# zero_board.net
KiCad netlist of a schematic drawn in EAGLE
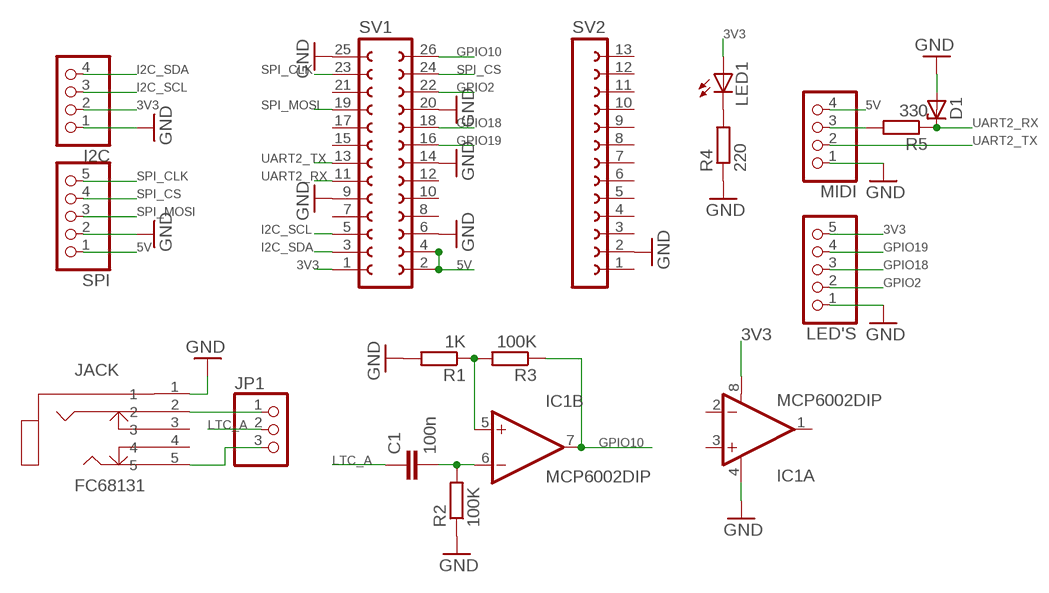
[diagram p0: schematic, sheet 1]

(export (version "E")
  (design (tool "Eeschema 10.0.6"))
  (components
    (comp (ref "C1")
      (value "100n")
      (footprint "eagle-import:C050-024X044")
      (libsource (lib "eagle-import") (part "C-EU050-024X044"))
    )
    (comp (ref "D1")
      (value "ZENER-DIODEZD-2.5")
      (footprint "eagle-import:ZDIO-2.5")
      (libsource (lib "eagle-import") (part "ZENER-DIODEZD-2.5"))
    )
    (comp (ref "I2C")
      (value "PINHD-1X4")
      (footprint "eagle-import:1X04")
      (libsource (lib "eagle-import") (part "PINHD-1X4"))
    )
    (comp (ref "IC1")
      (value "MCP6002DIP")
      (footprint "eagle-import:DIP08")
      (libsource (lib "eagle-import") (part "MCP6002DIP"))
    )
    (comp (ref "JACK")
      (value "FC68131")
      (footprint "eagle-import:FC68131-5P")
      (libsource (lib "eagle-import") (part "FC68131"))
    )
    (comp (ref "JP1")
      (value "PINHD-1X3")
      (footprint "eagle-import:1X03")
      (libsource (lib "eagle-import") (part "PINHD-1X3"))
    )
    (comp (ref "LED'S")
      (value "PINHD-1X5")
      (footprint "eagle-import:1X05")
      (libsource (lib "eagle-import") (part "PINHD-1X5"))
    )
    (comp (ref "LED1")
      (value "LED3MM")
      (footprint "eagle-import:LED3MM")
      (libsource (lib "eagle-import") (part "LED3MM"))
    )
    (comp (ref "MIDI")
      (value "PINHD-1X4")
      (footprint "eagle-import:1X04")
      (libsource (lib "eagle-import") (part "PINHD-1X4"))
    )
    (comp (ref "R1")
      (value "1K")
      (footprint "eagle-import:0204_5")
      (libsource (lib "eagle-import") (part "R-EU_0204/5"))
    )
    (comp (ref "R2")
      (value "100K")
      (footprint "eagle-import:0204_5")
      (libsource (lib "eagle-import") (part "R-EU_0204/5"))
    )
    (comp (ref "R3")
      (value "100K")
      (footprint "eagle-import:0204_5")
      (libsource (lib "eagle-import") (part "R-EU_0204/5"))
    )
    (comp (ref "R4")
      (value "220")
      (footprint "eagle-import:0204_5")
      (libsource (lib "eagle-import") (part "R-EU_0204/5"))
    )
    (comp (ref "R5")
      (value "330")
      (footprint "eagle-import:0204V")
      (libsource (lib "eagle-import") (part "R-EU_0204/2V"))
    )
    (comp (ref "SPI")
      (value "PINHD-1X5")
      (footprint "eagle-import:1X05")
      (libsource (lib "eagle-import") (part "PINHD-1X5"))
    )
    (comp (ref "SV1")
      (value "FE13-2")
      (footprint "eagle-import:FE13-2")
      (libsource (lib "eagle-import") (part "FE13-2"))
    )
    (comp (ref "SV2")
      (value "FE13-1")
      (footprint "eagle-import:FE13")
      (libsource (lib "eagle-import") (part "FE13-1"))
    )
  )
  (nets
    (net (code "1") (name "/3V3") (class "Default")
      (node (ref "I2C") (pin "2") (pinfunction "2_2") (pintype "passive"))
      (node (ref "IC1") (pin "8") (pinfunction "V+_8") (pintype "power_in"))
      (node (ref "LED'S") (pin "5") (pinfunction "5_5") (pintype "passive"))
      (node (ref "LED1") (pin "A") (pinfunction "A_A") (pintype "passive"))
      (node (ref "SV1") (pin "1") (pinfunction "1_1") (pintype "passive"))
    )
    (net (code "2") (name "/5V") (class "Default")
      (node (ref "MIDI") (pin "4") (pinfunction "4_4") (pintype "passive"))
      (node (ref "SPI") (pin "1") (pinfunction "1_1") (pintype "passive"))
      (node (ref "SV1") (pin "2") (pinfunction "2_2") (pintype "passive"))
      (node (ref "SV1") (pin "4") (pinfunction "4_4") (pintype "passive"))
    )
    (net (code "3") (name "/GPIO2") (class "Default")
      (node (ref "LED'S") (pin "2") (pinfunction "2_2") (pintype "passive"))
      (node (ref "SV1") (pin "22") (pinfunction "22_22") (pintype "passive"))
    )
    (net (code "4") (name "/GPIO10") (class "Default")
      (node (ref "IC1") (pin "7") (pinfunction "OUT_7") (pintype "output"))
      (node (ref "R3") (pin "1") (pinfunction "1_1") (pintype "passive"))
      (node (ref "SV1") (pin "26") (pinfunction "26_26") (pintype "passive"))
    )
    (net (code "5") (name "/GPIO18") (class "Default")
      (node (ref "LED'S") (pin "3") (pinfunction "3_3") (pintype "passive"))
      (node (ref "SV1") (pin "18") (pinfunction "18_18") (pintype "passive"))
    )
    (net (code "6") (name "/GPIO19") (class "Default")
      (node (ref "LED'S") (pin "4") (pinfunction "4_4") (pintype "passive"))
      (node (ref "SV1") (pin "16") (pinfunction "16_16") (pintype "passive"))
    )
    (net (code "7") (name "/I2C_SCL") (class "Default")
      (node (ref "I2C") (pin "3") (pinfunction "3_3") (pintype "passive"))
      (node (ref "SV1") (pin "5") (pinfunction "5_5") (pintype "passive"))
    )
    (net (code "8") (name "/I2C_SDA") (class "Default")
      (node (ref "I2C") (pin "4") (pinfunction "4_4") (pintype "passive"))
      (node (ref "SV1") (pin "3") (pinfunction "3_3") (pintype "passive"))
    )
    (net (code "9") (name "/LTC_A") (class "Default")
      (node (ref "C1") (pin "1") (pinfunction "1_1") (pintype "passive"))
      (node (ref "JP1") (pin "2") (pinfunction "2_2") (pintype "passive"))
    )
    (net (code "10") (name "/SPI_CLK") (class "Default")
      (node (ref "SPI") (pin "5") (pinfunction "5_5") (pintype "passive"))
      (node (ref "SV1") (pin "23") (pinfunction "23_23") (pintype "passive"))
    )
    (net (code "11") (name "/SPI_CS") (class "Default")
      (node (ref "SPI") (pin "4") (pinfunction "4_4") (pintype "passive"))
      (node (ref "SV1") (pin "24") (pinfunction "24_24") (pintype "passive"))
    )
    (net (code "12") (name "/SPI_MOSI") (class "Default")
      (node (ref "SPI") (pin "3") (pinfunction "3_3") (pintype "passive"))
      (node (ref "SV1") (pin "19") (pinfunction "19_19") (pintype "passive"))
    )
    (net (code "13") (name "/UART2_RX") (class "Default")
      (node (ref "D1") (pin "C") (pinfunction "C_C") (pintype "passive"))
      (node (ref "R5") (pin "1") (pinfunction "1_1") (pintype "passive"))
      (node (ref "SV1") (pin "11") (pinfunction "11_11") (pintype "passive"))
    )
    (net (code "14") (name "/UART2_TX") (class "Default")
      (node (ref "MIDI") (pin "2") (pinfunction "2_2") (pintype "passive"))
      (node (ref "SV1") (pin "13") (pinfunction "13_13") (pintype "passive"))
    )
    (net (code "15") (name "GND") (class "Default")
      (node (ref "D1") (pin "A") (pinfunction "A_A") (pintype "passive"))
      (node (ref "I2C") (pin "1") (pinfunction "1_1") (pintype "passive"))
      (node (ref "IC1") (pin "4") (pinfunction "V-_4") (pintype "power_in"))
      (node (ref "JACK") (pin "1") (pinfunction "1_1") (pintype "bidirectional"))
      (node (ref "LED'S") (pin "1") (pinfunction "1_1") (pintype "passive"))
      (node (ref "MIDI") (pin "1") (pinfunction "1_1") (pintype "passive"))
      (node (ref "R1") (pin "2") (pinfunction "2_2") (pintype "passive"))
      (node (ref "R2") (pin "1") (pinfunction "1_1") (pintype "passive"))
      (node (ref "R4") (pin "1") (pinfunction "1_1") (pintype "passive"))
      (node (ref "SPI") (pin "2") (pinfunction "2_2") (pintype "passive"))
      (node (ref "SV1") (pin "14") (pinfunction "14_14") (pintype "passive"))
      (node (ref "SV1") (pin "20") (pinfunction "20_20") (pintype "passive"))
      (node (ref "SV1") (pin "25") (pinfunction "25_25") (pintype "passive"))
      (node (ref "SV1") (pin "6") (pinfunction "6_6") (pintype "passive"))
      (node (ref "SV1") (pin "9") (pinfunction "9_9") (pintype "passive"))
      (node (ref "SV2") (pin "2") (pinfunction "2_2") (pintype "passive"))
    )
    (net (code "16") (name "Net-(IC1B-+IN)") (class "Default")
      (node (ref "IC1") (pin "5") (pinfunction "+IN_5") (pintype "input"))
      (node (ref "R1") (pin "1") (pinfunction "1_1") (pintype "passive"))
      (node (ref "R3") (pin "2") (pinfunction "2_2") (pintype "passive"))
    )
    (net (code "17") (name "Net-(IC1B--IN)") (class "Default")
      (node (ref "C1") (pin "2") (pinfunction "2_2") (pintype "passive"))
      (node (ref "IC1") (pin "6") (pinfunction "-IN_6") (pintype "input"))
      (node (ref "R2") (pin "2") (pinfunction "2_2") (pintype "passive"))
    )
    (net (code "18") (name "Net-(JACK-Pad2)") (class "Default")
      (node (ref "JACK") (pin "2") (pinfunction "2_2") (pintype "bidirectional"))
      (node (ref "JP1") (pin "1") (pinfunction "1_1") (pintype "passive"))
    )
    (net (code "19") (name "Net-(JACK-Pad5)") (class "Default")
      (node (ref "JACK") (pin "5") (pinfunction "5_5") (pintype "bidirectional"))
      (node (ref "JP1") (pin "3") (pinfunction "3_3") (pintype "passive"))
    )
    (net (code "20") (name "Net-(LED1-C)") (class "Default")
      (node (ref "LED1") (pin "K") (pinfunction "C_K") (pintype "passive"))
      (node (ref "R4") (pin "2") (pinfunction "2_2") (pintype "passive"))
    )
    (net (code "21") (name "Net-(MIDI-Pad3)") (class "Default")
      (node (ref "MIDI") (pin "3") (pinfunction "3_3") (pintype "passive"))
      (node (ref "R5") (pin "2") (pinfunction "2_2") (pintype "passive"))
    )
    (net (code "22") (name "unconnected-(IC1A-+IN-Pad3)") (class "Default")
      (node (ref "IC1") (pin "3") (pinfunction "+IN_3") (pintype "input"))
    )
    (net (code "23") (name "unconnected-(IC1A--IN-Pad2)") (class "Default")
      (node (ref "IC1") (pin "2") (pinfunction "-IN_2") (pintype "input"))
    )
    (net (code "24") (name "unconnected-(IC1A-OUT-Pad1)") (class "Default")
      (node (ref "IC1") (pin "1") (pinfunction "OUT_1") (pintype "output"))
    )
    (net (code "25") (name "unconnected-(JACK-Pad3)") (class "Default")
      (node (ref "JACK") (pin "3") (pinfunction "3_3") (pintype "bidirectional"))
    )
    (net (code "26") (name "unconnected-(JACK-Pad4)") (class "Default")
      (node (ref "JACK") (pin "4") (pinfunction "4_4") (pintype "bidirectional"))
    )
    (net (code "27") (name "unconnected-(SV1-Pad7)") (class "Default")
      (node (ref "SV1") (pin "7") (pinfunction "7_7") (pintype "passive"))
    )
    (net (code "28") (name "unconnected-(SV1-Pad8)") (class "Default")
      (node (ref "SV1") (pin "8") (pinfunction "8_8") (pintype "passive"))
    )
    (net (code "29") (name "unconnected-(SV1-Pad10)") (class "Default")
      (node (ref "SV1") (pin "10") (pinfunction "10_10") (pintype "passive"))
    )
    (net (code "30") (name "unconnected-(SV1-Pad12)") (class "Default")
      (node (ref "SV1") (pin "12") (pinfunction "12_12") (pintype "passive"))
    )
    (net (code "31") (name "unconnected-(SV1-Pad15)") (class "Default")
      (node (ref "SV1") (pin "15") (pinfunction "15_15") (pintype "passive"))
    )
    (net (code "32") (name "unconnected-(SV1-Pad17)") (class "Default")
      (node (ref "SV1") (pin "17") (pinfunction "17_17") (pintype "passive"))
    )
    (net (code "33") (name "unconnected-(SV1-Pad21)") (class "Default")
      (node (ref "SV1") (pin "21") (pinfunction "21_21") (pintype "passive"))
    )
    (net (code "34") (name "unconnected-(SV2-Pad1)") (class "Default")
      (node (ref "SV2") (pin "1") (pinfunction "1_1") (pintype "passive"))
    )
    (net (code "35") (name "unconnected-(SV2-Pad3)") (class "Default")
      (node (ref "SV2") (pin "3") (pinfunction "3_3") (pintype "passive"))
    )
    (net (code "36") (name "unconnected-(SV2-Pad4)") (class "Default")
      (node (ref "SV2") (pin "4") (pinfunction "4_4") (pintype "passive"))
    )
    (net (code "37") (name "unconnected-(SV2-Pad5)") (class "Default")
      (node (ref "SV2") (pin "5") (pinfunction "5_5") (pintype "passive"))
    )
    (net (code "38") (name "unconnected-(SV2-Pad6)") (class "Default")
      (node (ref "SV2") (pin "6") (pinfunction "6_6") (pintype "passive"))
    )
    (net (code "39") (name "unconnected-(SV2-Pad7)") (class "Default")
      (node (ref "SV2") (pin "7") (pinfunction "7_7") (pintype "passive"))
    )
    (net (code "40") (name "unconnected-(SV2-Pad8)") (class "Default")
      (node (ref "SV2") (pin "8") (pinfunction "8_8") (pintype "passive"))
    )
    (net (code "41") (name "unconnected-(SV2-Pad9)") (class "Default")
      (node (ref "SV2") (pin "9") (pinfunction "9_9") (pintype "passive"))
    )
    (net (code "42") (name "unconnected-(SV2-Pad10)") (class "Default")
      (node (ref "SV2") (pin "10") (pinfunction "10_10") (pintype "passive"))
    )
    (net (code "43") (name "unconnected-(SV2-Pad11)") (class "Default")
      (node (ref "SV2") (pin "11") (pinfunction "11_11") (pintype "passive"))
    )
    (net (code "44") (name "unconnected-(SV2-Pad12)") (class "Default")
      (node (ref "SV2") (pin "12") (pinfunction "12_12") (pintype "passive"))
    )
    (net (code "45") (name "unconnected-(SV2-Pad13)") (class "Default")
      (node (ref "SV2") (pin "13") (pinfunction "13_13") (pintype "passive"))
    )
  )
)
